# Motor-Supply-Section.net
KiCad netlist of a schematic drawn in Altium Designer
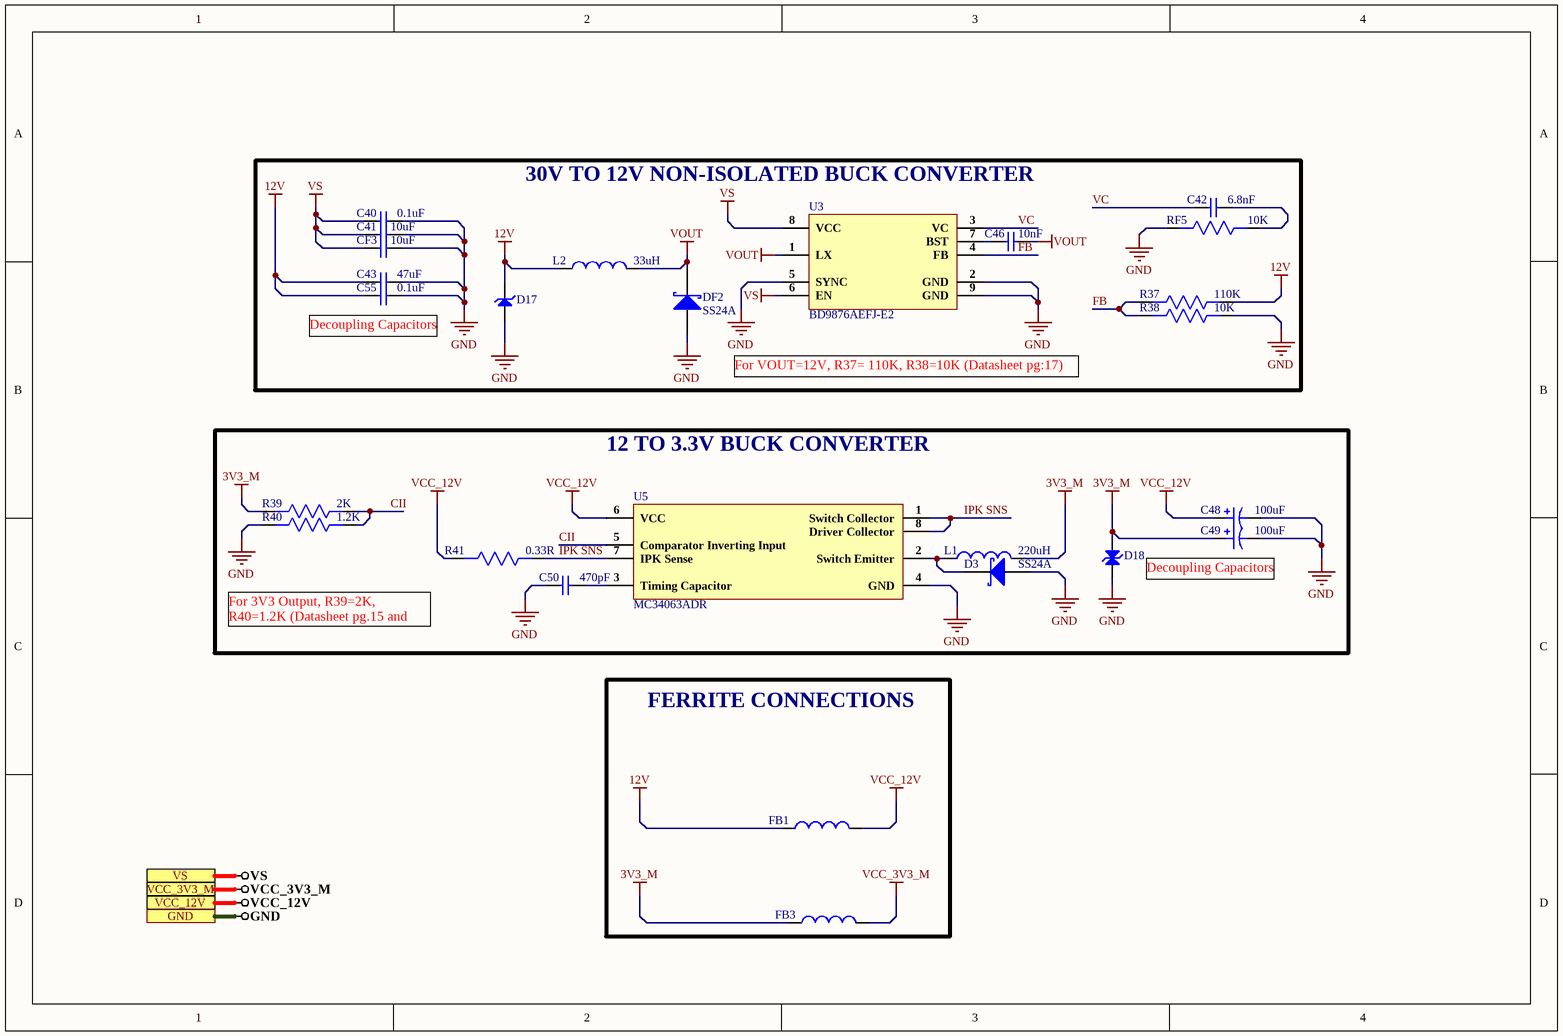
[diagram p0: Motor-Supply-Section.SchDoc]

(export (version "E")
  (design (tool "Eeschema 10.0.6"))
  (components
    (comp (ref "C40")
      (value "0.1uF")
      (footprint "Cap 0603")
      (description "Cap Ceramic 0.1uF 50VDC X7R 10% SMD 0603 Paper T/R")
      (fields
        (field (name "MANUFACTURER") "Samsung")
        (field (name "MANUFACTURER PART NUMBER") "CL10B104KB8NNNC")
      )
      (libsource (lib "Cole_Benson") (part "CL10B104KB8NNNC"))
    )
    (comp (ref "C41")
      (value "10uF")
      (footprint "Cap0805")
      (description "CAP CER 10UF 50V X5R 0805")
      (fields
        (field (name "MANUFACTURER") "Samsung")
        (field (name "MANUFACTURER PART NUMBER") "CL21A106KBYQNNE")
      )
      (libsource (lib "Cole_Benson") (part "CL21A106KBYQNNE"))
    )
    (comp (ref "C42")
      (value "6.8nF")
      (footprint "Cap 0603")
      (description "50V 6.8nF X7R ±10% 0603")
      (fields (field (name "MANUFACTURER") "FH") (field (name "MANUFACTURER PART NUMBER") "0603B682K500NT"))
      (libsource (lib "Cole_Benson") (part "0603B682K500NT"))
    )
    (comp (ref "C43")
      (value "47uF")
      (footprint "Cap1206")
      (description "CAP CER 1206 47 uF 25 V ±20 % Tol. X5R")
      (fields
        (field (name "MANUFACTURER") "Murata")
        (field (name "MANUFACTURER PART NUMBER") "GRM31CR61E476ME44L")
      )
      (libsource (lib "Cole_Benson") (part "GRM31CR61E476ME44L"))
    )
    (comp (ref "C46")
      (value "10nF")
      (footprint "Cap 0402")
      (description "CAP CER 10000PF 25V X7R 0402")
      (fields
        (field (name "MANUFACTURER") "Yageo")
        (field (name "MANUFACTURER PART NUMBER") "CC0402KRX7R8BB103")
      )
      (libsource (lib "Cole_Benson") (part "CC0402KRX7R8BB103"))
    )
    (comp (ref "C48")
      (value "100uF")
      (footprint "CAP- 2917")
      (description "CAP TANT 100UF 20% 25V 2917")
      (fields
        (field (name "MANUFACTURER") "Kyocera AVX")
        (field (name "MANUFACTURER PART NUMBER") "TAJE107M025RNJ")
      )
      (libsource (lib "Cole_Benson") (part "TAJE107M025RNJ"))
    )
    (comp (ref "C49")
      (value "100uF")
      (footprint "CAP- 2917")
      (description "CAP TANT 100UF 20% 25V 2917")
      (fields
        (field (name "MANUFACTURER") "Kyocera AVX")
        (field (name "MANUFACTURER PART NUMBER") "TAJE107M025RNJ")
      )
      (libsource (lib "Cole_Benson") (part "TAJE107M025RNJ"))
    )
    (comp (ref "C50")
      (value "470pF")
      (footprint "Cap 0603")
      (description "CAP CER 470pF 10% X7R 50V 0603 SMD")
      (fields
        (field (name "MANUFACTURER") "Yageo")
        (field (name "MANUFACTURER PART NUMBER") "CC0603KRX7R9BB471")
      )
      (libsource (lib "Cole_Benson") (part "CC0603KRX7R9BB471"))
    )
    (comp (ref "C55")
      (value "0.1uF")
      (footprint "Cap 0603")
      (description "Cap Ceramic 0.1uF 50VDC X7R 10% SMD 0603 Paper T/R")
      (fields
        (field (name "MANUFACTURER") "Samsung")
        (field (name "MANUFACTURER PART NUMBER") "CL10B104KB8NNNC")
      )
      (libsource (lib "Cole_Benson") (part "CL10B104KB8NNNC"))
    )
    (comp (ref "CF3")
      (value "10uF")
      (footprint "Cap0805")
      (description "CAP CER 10UF 50V X5R 0805")
      (fields
        (field (name "MANUFACTURER") "Samsung")
        (field (name "MANUFACTURER PART NUMBER") "CL21A106KBYQNNE")
      )
      (libsource (lib "Cole_Benson") (part "CL21A106KBYQNNE"))
    )
    (comp (ref "D3")
      (value "SS24A")
      (footprint "SMA")
      (description "40V 500mV@2A 2A SMA(DO-214AC) Schottky Barrier Diodes (SBD) ROHS")
      (fields (field (name "MANUFACTURER") "Yangzhou"))
      (libsource (lib "Cole_Benson") (part "SS24A"))
    )
    (comp (ref "D17")
      (value "MSMP12A-M3/89A")
      (footprint "MicroSMP")
      (description "TVS DIODE 12VWM 19.9VC MICROSMP")
      (fields (field (name "LCSC PART NUMBER") "C1973858"))
      (libsource (lib "Cole_Benson") (part "MSMP12A-M3/89A"))
    )
    (comp (ref "D18")
      (value "ESDM2033MX4T5G")
      (footprint "2-DFN (0.6x0.3)")
      (description "DIODE BIDIR ESD X4DFN2")
      (fields (field (name "MANUFACTURER") "ON Semiconductor") (field (name "LCSC PART NUMBER") "C896720"))
      (libsource (lib "Cole_Benson") (part "ESDM2033MX4T5G"))
    )
    (comp (ref "DF2")
      (value "SS24A")
      (footprint "SMA")
      (description "40V 500mV@2A 2A SMA(DO-214AC) Schottky Barrier Diodes (SBD) ROHS")
      (fields (field (name "MANUFACTURER") "Yangzhou"))
      (libsource (lib "Cole_Benson") (part "SS24A"))
    )
    (comp (ref "FB1")
      (value "MPZ1608S121ATDH5")
      (footprint "MPZ1608S121ATDH5")
      (description "Ferrite Beads Multi-Layer 120Ohm 25% 100MHz 2A 45mOhm DCR 0603 Automotive T/R")
      (fields (field (name "MANUFACTURER") "TDK") (field (name "TOLERANCE") "25%"))
      (libsource (lib "Cole_Benson") (part "MPZ1608S121ATDH5"))
    )
    (comp (ref "FB3")
      (value "MPZ1608S121ATDH5")
      (footprint "MPZ1608S121ATDH5")
      (description "Ferrite Beads Multi-Layer 120Ohm 25% 100MHz 2A 45mOhm DCR 0603 Automotive T/R")
      (fields (field (name "MANUFACTURER") "TDK") (field (name "TOLERANCE") "25%"))
      (libsource (lib "Cole_Benson") (part "MPZ1608S121ATDH5"))
    )
    (comp (ref "L1")
      (value "220uH")
      (footprint "SLF12575T-221M1R3-PF")
      (description "Inductor Power Shielded Wirewound 220uH 20% 1KHz Ferrite 1.3A 310mOhm DCR Blister T/R")
      (fields
        (field (name "MANUFACTURER") "TDK")
        (field (name "MANUFACTURER PART NUMBER") "SLF12575T-221M1R3-PF")
      )
      (libsource (lib "Cole_Benson") (part "SLF12575T-221M1R3-PF"))
    )
    (comp (ref "L2")
      (value "33uH")
      (footprint "PNLS5020-330")
      (description "1A 33uH ±20% 356mΩ SMD,5x5x2mm Power Inductors ROHS")
      (fields (field (name "MANUFACTURER") "DMBJ") (field (name "MANUFACTURER PART NUMBER") "PNLS5020-330"))
      (libsource (lib "Cole_Benson") (part "PNLS5020-330"))
    )
    (comp (ref "R37")
      (value "110K")
      (footprint "Res0603")
      (description "110kΩ 0603 Chip Resistor - Surface Mount ROHS")
      (fields
        (field (name "MANUFACTURER") "UNI-ROYAL")
        (field (name "MANUFACTURER PART NUMBER") "0603WAD1103T5E")
      )
      (libsource (lib "Cole_Benson") (part "0603WAD1103T5E"))
    )
    (comp (ref "R38")
      (value "10K")
      (footprint "Res0603")
      (description "RES SMD 10K Ohm 1% 1/10W 0603")
      (fields
        (field (name "MANUFACTURER") "Yageo")
        (field (name "MANUFACTURER PART NUMBER") "RC0603FR-0710KL")
      )
      (libsource (lib "Cole_Benson") (part "RC0603FR-0710KL"))
    )
    (comp (ref "R39")
      (value "2K")
      (footprint "Res0603")
      (description "RES SMD 2K OHM 1% 1/10W 0603")
      (fields
        (field (name "MANUFACTURER") "Yageo")
        (field (name "MANUFACTURER PART NUMBER") "RC0603FR-072KL")
      )
      (libsource (lib "Cole_Benson") (part "RC0603FR-072KL"))
    )
    (comp (ref "R40")
      (value "1.2K")
      (footprint "Res0603")
      (fields
        (field (name "MANUFACTURER") "UNI-ROYAL")
        (field (name "MANUFACTURER PART NO") "0603WAF1201T5E")
      )
      (libsource (lib "Cole_Benson") (part "0603WAF1201T5E"))
    )
    (comp (ref "R41")
      (value "0.33R")
      (footprint "Res0603")
      (fields (field (name "MANUFACTURER") "RALEC") (field (name "MANUFACTURER PART NO") "RTT03R330FTP"))
      (libsource (lib "Cole_Benson") (part "RTT03R330FTP"))
    )
    (comp (ref "RF5")
      (value "10K")
      (footprint "Res0603")
      (description "RES SMD 10K Ohm 1% 1/10W 0603")
      (fields
        (field (name "MANUFACTURER") "Yageo")
        (field (name "MANUFACTURER PART NUMBER") "RC0603FR-0710KL")
      )
      (libsource (lib "Cole_Benson") (part "RC0603FR-0710KL"))
    )
    (comp (ref "U3")
      (value "BD9876AEFJ-E2")
      (footprint "8-HTSOP-J")
      (description "NO Step-down type 1 Step-down 1V~29.4V 7V~42V 3A 300kHz SOIC-8_EP_150mil DC-DC Converters ROHS")
      (fields (field (name "MANUFACTURER") "ROHM Semicon"))
      (libsource (lib "Cole_Benson") (part "BD9876AEFJ-E2"))
    )
    (comp (ref "U5")
      (value "MC34063ADR")
      (footprint "SOIC-8")
      (description "1.5-A boost, buck, inverting switching regulator, operation from 0°C to 70°C 8-SOIC 0 to 70")
      (fields (field (name "MANUFACTURER") "Texas Instruments"))
      (libsource (lib "Cole_Benson") (part "MC34063ADR"))
    )
  )
  (nets
    (net (code "1") (name "/CII") (class "Default")
      (node (ref "R39") (pin "1") (pintype "passive"))
      (node (ref "R40") (pin "1") (pintype "passive"))
      (node (ref "U5") (pin "5") (pinfunction "Comparator_Inverting_Input_5") (pintype "passive"))
    )
    (net (code "2") (name "/FB") (class "Default")
      (node (ref "R37") (pin "2") (pintype "passive"))
      (node (ref "R38") (pin "2") (pintype "passive"))
      (node (ref "U3") (pin "4") (pinfunction "FB_4") (pintype "passive"))
    )
    (net (code "3") (name "/IPK SNS") (class "Default")
      (node (ref "R41") (pin "1") (pintype "passive"))
      (node (ref "U5") (pin "1") (pinfunction "Switch_Collector_1") (pintype "passive"))
      (node (ref "U5") (pin "7") (pinfunction "IPK_Sense_7") (pintype "passive"))
      (node (ref "U5") (pin "8") (pinfunction "Driver_Collector_8") (pintype "passive"))
    )
    (net (code "4") (name "/VC") (class "Default")
      (node (ref "C42") (pin "1") (pinfunction "1_1") (pintype "passive"))
      (node (ref "U3") (pin "3") (pinfunction "VC_3") (pintype "passive"))
    )
    (net (code "5") (name "3V3_M") (class "Default")
      (node (ref "C49") (pin "1") (pinfunction "1_1") (pintype "passive"))
      (node (ref "D18") (pin "2") (pinfunction "A_2") (pintype "passive"))
      (node (ref "FB3") (pin "1") (pinfunction "1_1") (pintype "passive"))
      (node (ref "L1") (pin "2") (pinfunction "2_2") (pintype "passive"))
      (node (ref "R39") (pin "2") (pintype "passive"))
    )
    (net (code "6") (name "12V") (class "Default")
      (node (ref "C43") (pin "1") (pinfunction "1_1") (pintype "passive"))
      (node (ref "C55") (pin "1") (pinfunction "1_1") (pintype "passive"))
      (node (ref "D17") (pin "2") (pinfunction "K_2") (pintype "passive"))
      (node (ref "FB1") (pin "1") (pinfunction "1_1") (pintype "passive"))
      (node (ref "L2") (pin "1") (pinfunction "1_1") (pintype "passive"))
      (node (ref "R37") (pin "1") (pintype "passive"))
    )
    (net (code "7") (name "GND") (class "Default")
      (node (ref "C40") (pin "2") (pinfunction "2_2") (pintype "passive"))
      (node (ref "C41") (pin "1") (pinfunction "1_1") (pintype "passive"))
      (node (ref "C43") (pin "2") (pinfunction "2_2") (pintype "passive"))
      (node (ref "C48") (pin "2") (pinfunction "2_2") (pintype "passive"))
      (node (ref "C49") (pin "2") (pinfunction "2_2") (pintype "passive"))
      (node (ref "C50") (pin "1") (pinfunction "1_1") (pintype "passive"))
      (node (ref "C55") (pin "2") (pinfunction "2_2") (pintype "passive"))
      (node (ref "CF3") (pin "1") (pinfunction "1_1") (pintype "passive"))
      (node (ref "D17") (pin "1") (pinfunction "A_1") (pintype "passive"))
      (node (ref "D18") (pin "1") (pinfunction "A_1") (pintype "passive"))
      (node (ref "D3") (pin "2") (pinfunction "A_2") (pintype "passive"))
      (node (ref "DF2") (pin "2") (pinfunction "A_2") (pintype "passive"))
      (node (ref "R38") (pin "1") (pintype "passive"))
      (node (ref "R40") (pin "2") (pintype "passive"))
      (node (ref "RF5") (pin "2") (pintype "passive"))
      (node (ref "U3") (pin "2") (pinfunction "GND_2") (pintype "passive"))
      (node (ref "U3") (pin "5") (pinfunction "SYNC_5") (pintype "passive"))
      (node (ref "U3") (pin "9") (pinfunction "GND_9") (pintype "passive"))
      (node (ref "U5") (pin "4") (pinfunction "GND_4") (pintype "passive"))
    )
    (net (code "8") (name "Net-(C42-Pad2)") (class "Default")
      (node (ref "C42") (pin "2") (pinfunction "2_2") (pintype "passive"))
      (node (ref "RF5") (pin "1") (pintype "passive"))
    )
    (net (code "9") (name "Net-(D3-K)") (class "Default")
      (node (ref "D3") (pin "1") (pinfunction "K_1") (pintype "passive"))
      (node (ref "L1") (pin "1") (pinfunction "1_1") (pintype "passive"))
      (node (ref "U5") (pin "2") (pinfunction "Switch_Emitter_2") (pintype "passive"))
    )
    (net (code "10") (name "Net-(U3-BST)") (class "Default")
      (node (ref "C46") (pin "1") (pinfunction "1_1") (pintype "passive"))
      (node (ref "U3") (pin "7") (pinfunction "BST_7") (pintype "passive"))
    )
    (net (code "11") (name "Net-(U5-Timing_Capacitor)") (class "Default")
      (node (ref "C50") (pin "2") (pinfunction "2_2") (pintype "passive"))
      (node (ref "U5") (pin "3") (pinfunction "Timing_Capacitor_3") (pintype "passive"))
    )
    (net (code "12") (name "VCC_3V3_M") (class "Default")
      (node (ref "FB3") (pin "2") (pinfunction "2_2") (pintype "passive"))
    )
    (net (code "13") (name "VCC_12V") (class "Default")
      (node (ref "C48") (pin "1") (pinfunction "1_1") (pintype "passive"))
      (node (ref "FB1") (pin "2") (pinfunction "2_2") (pintype "passive"))
      (node (ref "R41") (pin "2") (pintype "passive"))
      (node (ref "U5") (pin "6") (pinfunction "VCC_6") (pintype "passive"))
    )
    (net (code "14") (name "VOUT") (class "Default")
      (node (ref "C46") (pin "2") (pinfunction "2_2") (pintype "passive"))
      (node (ref "DF2") (pin "1") (pinfunction "K_1") (pintype "passive"))
      (node (ref "L2") (pin "2") (pinfunction "2_2") (pintype "passive"))
      (node (ref "U3") (pin "1") (pinfunction "LX_1") (pintype "passive"))
    )
    (net (code "15") (name "VS") (class "Default")
      (node (ref "C40") (pin "1") (pinfunction "1_1") (pintype "passive"))
      (node (ref "C41") (pin "2") (pinfunction "2_2") (pintype "passive"))
      (node (ref "CF3") (pin "2") (pinfunction "2_2") (pintype "passive"))
      (node (ref "U3") (pin "6") (pinfunction "EN_6") (pintype "passive"))
      (node (ref "U3") (pin "8") (pinfunction "VCC_8") (pintype "passive"))
    )
  )
)
